# 19-100M_Ethernet.net
KiCad netlist of a schematic drawn in Altium Designer
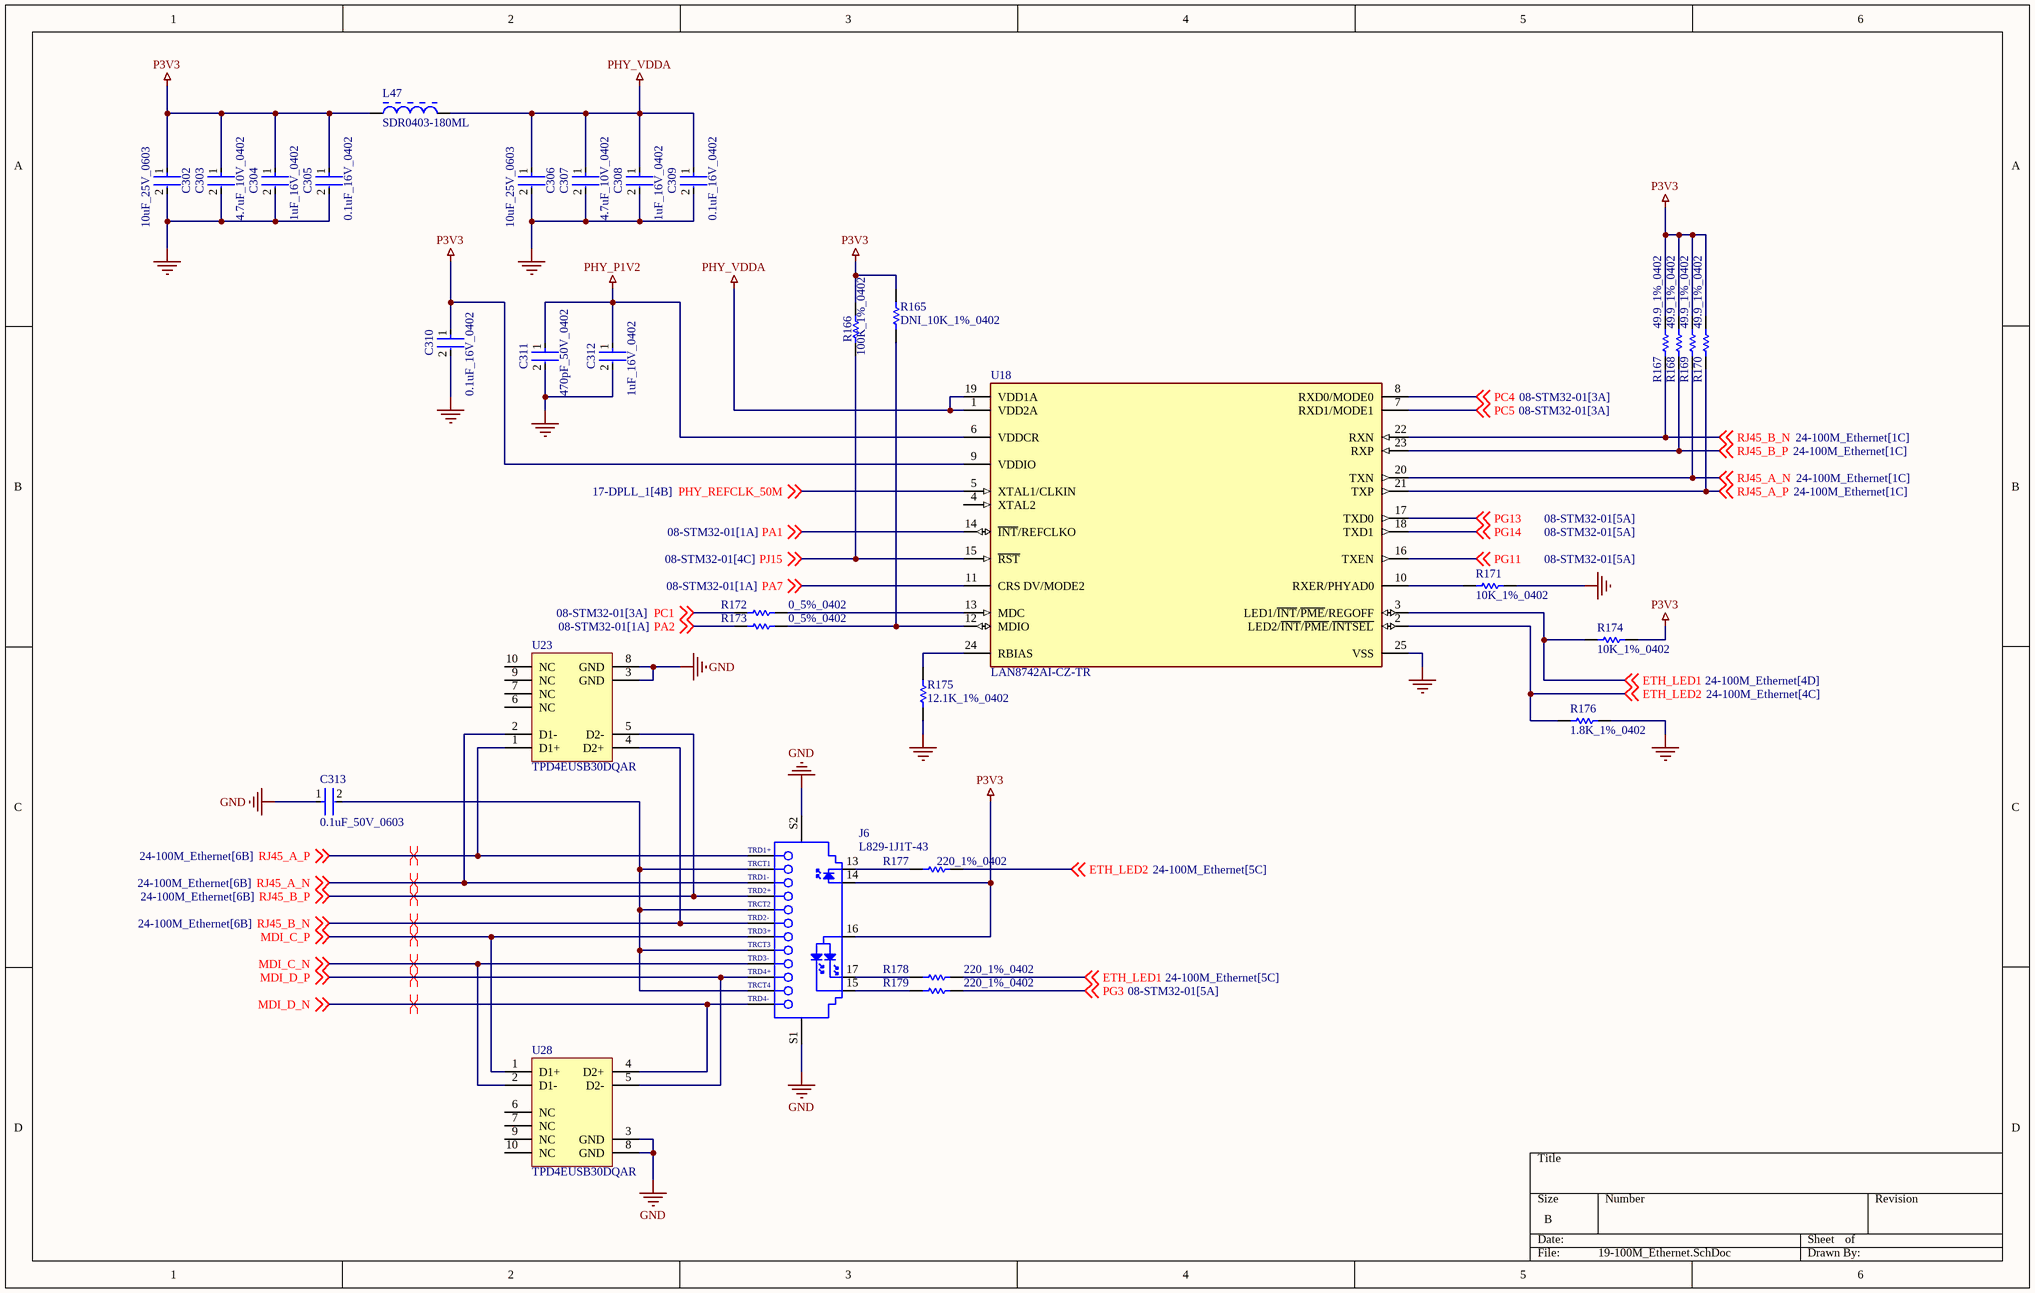
[diagram p0: 19-100M_Ethernet.SchDoc]

(export (version "E")
  (design (tool "Eeschema 10.0.6"))
  (components
    (comp (ref "C302")
      (value "10uF_25V_0603")
      (footprint "FP-CL10-IPC_C")
      (description "Cap Ceramic 10uF 25V X5R ±20% Pad SMD 0603 +85°C T/R")
      (fields (field (name "TOLERANCE") "20%"))
      (libsource (lib "Altium Content Vault") (part "b4654b650e69147ec39a6b967a45e02"))
    )
    (comp (ref "C303")
      (value "4.7uF_10V_0402")
      (footprint "FP-C1005-050-0_15-MFG")
      (description "CAP CER 4.7UF 10V X5R 0402")
      (fields (field (name "TOLERANCE") "10%"))
      (libsource (lib "Altium Content Vault") (part "b4654b650e69147ec39a6b967a45e02"))
    )
    (comp (ref "C304")
      (value "1uF_16V_0402")
      (footprint "FP-0402-L_1_0_0_05-W_0_5-IPC_A")
      (description "None")
      (fields (field (name "TOLERANCE") "10%"))
      (libsource (lib "Altium Content Vault") (part "b4654b650e69147ec39a6b967a45e02"))
    )
    (comp (ref "C305")
      (value "0.1uF_16V_0402")
      (footprint "FP-C0402-BB-MFG")
      (description "CAP CER 0.1UF 16V 5% X7R 0402")
      (fields
        (field (name "MANUFACTURER") "Kemet")
        (field (name "MANUFACTURER PART NUMBER") "C0402C104J4RACTU")
      )
      (libsource (lib "Altium Content Vault") (part "b4654b650e69147ec39a6b967a45e02"))
    )
    (comp (ref "C306")
      (value "10uF_25V_0603")
      (footprint "FP-CL10-IPC_C")
      (description "Cap Ceramic 10uF 25V X5R ±20% Pad SMD 0603 +85°C T/R")
      (fields (field (name "TOLERANCE") "20%"))
      (libsource (lib "Altium Content Vault") (part "b4654b650e69147ec39a6b967a45e02"))
    )
    (comp (ref "C307")
      (value "4.7uF_10V_0402")
      (footprint "FP-C1005-050-0_15-MFG")
      (description "CAP CER 4.7UF 10V X5R 0402")
      (fields (field (name "TOLERANCE") "10%"))
      (libsource (lib "Altium Content Vault") (part "b4654b650e69147ec39a6b967a45e02"))
    )
    (comp (ref "C308")
      (value "1uF_16V_0402")
      (footprint "FP-0402-L_1_0_0_05-W_0_5-IPC_A")
      (description "None")
      (fields (field (name "TOLERANCE") "10%"))
      (libsource (lib "Altium Content Vault") (part "b4654b650e69147ec39a6b967a45e02"))
    )
    (comp (ref "C309")
      (value "0.1uF_16V_0402")
      (footprint "FP-C0402-BB-MFG")
      (description "CAP CER 0.1UF 16V 5% X7R 0402")
      (fields
        (field (name "MANUFACTURER") "Kemet")
        (field (name "MANUFACTURER PART NUMBER") "C0402C104J4RACTU")
      )
      (libsource (lib "Altium Content Vault") (part "b4654b650e69147ec39a6b967a45e02"))
    )
    (comp (ref "C310")
      (value "0.1uF_16V_0402")
      (footprint "FP-C0402-BB-MFG")
      (description "CAP CER 0.1UF 16V 5% X7R 0402")
      (fields
        (field (name "MANUFACTURER") "Kemet")
        (field (name "MANUFACTURER PART NUMBER") "C0402C104J4RACTU")
      )
      (libsource (lib "Altium Content Vault") (part "b4654b650e69147ec39a6b967a45e02"))
    )
    (comp (ref "C311")
      (value "470pF_50V_0402")
      (footprint "FP-GRM155-0_05-IPC_A")
      (description "Chip Multilayer Ceramic Capacitors for General Purpose, 0402, 470pF, C0G, 30ppm/°C, 5%, 50V")
      (fields (field (name "VOLTAGE") "50V") (field (name "TOLERANCE") "5%"))
      (libsource (lib "Altium Content Vault") (part "02cd4be3c70576c341d710602a673aa"))
    )
    (comp (ref "C312")
      (value "1uF_16V_0402")
      (footprint "FP-0402-L_1_0_0_05-W_0_5-IPC_A")
      (description "None")
      (fields (field (name "TOLERANCE") "10%"))
      (libsource (lib "Altium Content Vault") (part "b4654b650e69147ec39a6b967a45e02"))
    )
    (comp (ref "C313")
      (value "0.1uF_50V_0603")
      (footprint "FP-C0603-CJ-MFG")
      (description "CAP CER 0.1UF 50V X7R 0603")
      (fields (field (name "MANUFACTURER PART NUMBER") "C0603X104K5RACTU") (field (name "VOLTAGE") "50V"))
      (libsource (lib "Altium Content Vault") (part "11868f565c42a9108669ba33697ecf6"))
    )
    (comp (ref "J6")
      (value "L829-1J1T-43")
      (footprint "BELS-L829-1J1T-43_V")
      (description "Gigabit MagJack(R) Ultra Low Profile, 10/100/1000 Base-T, 19-Pin THD, RoHS, Tray")
      (libsource (lib "Altium Content Vault") (part "RJ45-17-2SHLD"))
    )
    (comp (ref "L47")
      (value "SDR0403-180ML")
      (footprint "BOUR-SDR0403-2_V")
      (fields (field (name "MANUFACTURER") "Bourns"))
      (libsource (lib "Altium Content Vault") (part "BOUR-IND-2A"))
    )
    (comp (ref "R165")
      (value "DNI_10K_1%_0402")
      (footprint "RESC1005X40X25NL10T10")
      (fields (field (name "MANUFACTURER") "Bourns") (field (name "PART NUMBER") "CR0402-FX-1002GLF"))
      (libsource (lib "Altium Content Vault") (part "RES"))
    )
    (comp (ref "R166")
      (value "100K_1%_0402")
      (footprint "RESC1005X40X25ML05T10")
      (fields (field (name "MANUFACTURER") "Yageo") (field (name "PART NUMBER") "RC0402FR-13100KL"))
      (libsource (lib "Altium Content Vault") (part "RES"))
    )
    (comp (ref "R167")
      (value "49.9_1%_0402")
      (footprint "RESC1005X40X25NL10T10")
      (fields (field (name "PART NUMBER") "RK73H1ETTP49R9F") (field (name "MANUFACTURER") "KOA Speer"))
      (libsource (lib "Altium Content Vault") (part "RES"))
    )
    (comp (ref "R168")
      (value "49.9_1%_0402")
      (footprint "RESC1005X40X25NL10T10")
      (fields (field (name "PART NUMBER") "RK73H1ETTP49R9F") (field (name "MANUFACTURER") "KOA Speer"))
      (libsource (lib "Altium Content Vault") (part "RES"))
    )
    (comp (ref "R169")
      (value "49.9_1%_0402")
      (footprint "RESC1005X40X25NL10T10")
      (fields (field (name "PART NUMBER") "RK73H1ETTP49R9F") (field (name "MANUFACTURER") "KOA Speer"))
      (libsource (lib "Altium Content Vault") (part "RES"))
    )
    (comp (ref "R170")
      (value "49.9_1%_0402")
      (footprint "RESC1005X40X25NL10T10")
      (fields (field (name "PART NUMBER") "RK73H1ETTP49R9F") (field (name "MANUFACTURER") "KOA Speer"))
      (libsource (lib "Altium Content Vault") (part "RES"))
    )
    (comp (ref "R171")
      (value "10K_1%_0402")
      (footprint "RESC1005X40X25NL10T10")
      (fields (field (name "MANUFACTURER") "Bourns") (field (name "PART NUMBER") "CR0402-FX-1002GLF"))
      (libsource (lib "Altium Content Vault") (part "RES"))
    )
    (comp (ref "R172")
      (value "0_5%_0402")
      (footprint "RESC1005X40X25NL05T10")
      (fields (field (name "MANUFACTURER") "Panasonic") (field (name "PART NUMBER") "ERJ-U020R00X"))
      (libsource (lib "Altium Content Vault") (part "RES"))
    )
    (comp (ref "R173")
      (value "0_5%_0402")
      (footprint "RESC1005X40X25NL05T10")
      (fields (field (name "MANUFACTURER") "Panasonic") (field (name "PART NUMBER") "ERJ-U020R00X"))
      (libsource (lib "Altium Content Vault") (part "RES"))
    )
    (comp (ref "R174")
      (value "10K_1%_0402")
      (footprint "RESC1005X40X25NL10T10")
      (fields (field (name "MANUFACTURER") "Bourns") (field (name "PART NUMBER") "CR0402-FX-1002GLF"))
      (libsource (lib "Altium Content Vault") (part "RES"))
    )
    (comp (ref "R175")
      (value "12.1K_1%_0402")
      (footprint "RESC1005X40X25ML05T10")
      (fields (field (name "PART NUMBER") "RC0402FR-0712K1L") (field (name "MANUFACTURER") "Yageo / Phycomp"))
      (libsource (lib "Altium Content Vault") (part "RES"))
    )
    (comp (ref "R176")
      (value "1.8K_1%_0402")
      (footprint "RESC1005X40X25LL05T05")
      (fields (field (name "MANUFACTURER") "Panasonic") (field (name "PART NUMBER") "ERJ2RKF1801X"))
      (libsource (lib "Altium Content Vault") (part "RES"))
    )
    (comp (ref "R177")
      (value "220_1%_0402")
      (footprint "RESC1005X40X25LL10T10")
      (fields (field (name "PART NUMBER") "RK73H1ETTP2200F") (field (name "MANUFACTURER") "KOA Speer"))
      (libsource (lib "Altium Content Vault") (part "RES"))
    )
    (comp (ref "R178")
      (value "220_1%_0402")
      (footprint "RESC1005X40X25LL10T10")
      (fields (field (name "PART NUMBER") "RK73H1ETTP2200F") (field (name "MANUFACTURER") "KOA Speer"))
      (libsource (lib "Altium Content Vault") (part "RES"))
    )
    (comp (ref "R179")
      (value "220_1%_0402")
      (footprint "RESC1005X40X25LL10T10")
      (fields (field (name "PART NUMBER") "RK73H1ETTP2200F") (field (name "MANUFACTURER") "KOA Speer"))
      (libsource (lib "Altium Content Vault") (part "RES"))
    )
    (comp (ref "U18")
      (value "LAN8742AI-CZ-TR")
      (footprint "FP-C04-143-MFG")
      (description "IC TRANSCEIVER FULL 1/1 24SQFN")
      (fields
        (field (name "MANUFACTURER") "Microchip")
        (field (name "OCTOPART") "https://octopart.com/lan8742ai-cz-tr-microchip-29030589")
      )
      (libsource (lib "Altium Content Vault") (part "663acb86b5908f69048389f16eb1286"))
    )
    (comp (ref "U23")
      (value "TPD4EUSB30DQAR")
      (footprint "DQA0010A_V")
      (fields (field (name "MANUFACTURER") "Texas Instruments"))
      (libsource (lib "") (part "TI-TPD4EUSB30-SON_DQA-10_1"))
    )
    (comp (ref "U28")
      (value "TPD4EUSB30DQAR")
      (footprint "DQA0010A_V")
      (fields (field (name "MANUFACTURER") "Texas Instruments"))
      (libsource (lib "Altium Content Vault") (part "TI-TPD4EUSB30-SON_DQA-10"))
    )
  )
  (nets
    (net (code "1") (name "ETH_LED1") (class "Default")
      (node (ref "R174") (pin "2") (pinfunction "2_2") (pintype "passive"))
      (node (ref "R178") (pin "2") (pinfunction "2_2") (pintype "passive"))
      (node (ref "U18") (pin "3") (pinfunction "LED1/~{INT}/~{PME}/REGOFF_3") (pintype "bidirectional"))
    )
    (net (code "2") (name "ETH_LED2") (class "Default")
      (node (ref "R176") (pin "1") (pinfunction "1_1") (pintype "passive"))
      (node (ref "R177") (pin "2") (pinfunction "2_2") (pintype "passive"))
      (node (ref "U18") (pin "2") (pinfunction "LED2/~{INT}/~{PME}/~{INTSEL}_2") (pintype "bidirectional"))
    )
    (net (code "3") (name "GND") (class "Default")
      (node (ref "C302") (pin "2") (pinfunction "2_2") (pintype "passive"))
      (node (ref "C303") (pin "2") (pinfunction "2_2") (pintype "passive"))
      (node (ref "C304") (pin "2") (pinfunction "2_2") (pintype "passive"))
      (node (ref "C305") (pin "2") (pinfunction "2_2") (pintype "passive"))
      (node (ref "C306") (pin "2") (pinfunction "2_2") (pintype "passive"))
      (node (ref "C307") (pin "2") (pinfunction "2_2") (pintype "passive"))
      (node (ref "C308") (pin "2") (pinfunction "2_2") (pintype "passive"))
      (node (ref "C309") (pin "2") (pinfunction "2_2") (pintype "passive"))
      (node (ref "C310") (pin "2") (pinfunction "2_2") (pintype "passive"))
      (node (ref "C311") (pin "2") (pinfunction "2_2") (pintype "passive"))
      (node (ref "C312") (pin "2") (pinfunction "2_2") (pintype "passive"))
      (node (ref "C313") (pin "1") (pinfunction "1_1") (pintype "passive"))
      (node (ref "J6") (pin "S1") (pinfunction "S1_S1") (pintype "passive"))
      (node (ref "J6") (pin "S2") (pinfunction "S2_S2") (pintype "passive"))
      (node (ref "R171") (pin "1") (pinfunction "1_1") (pintype "passive"))
      (node (ref "R175") (pin "1") (pinfunction "1_1") (pintype "passive"))
      (node (ref "R176") (pin "2") (pinfunction "2_2") (pintype "passive"))
      (node (ref "U18") (pin "25") (pinfunction "VSS_25") (pintype "power_in"))
      (node (ref "U23") (pin "3") (pinfunction "GND_3") (pintype "power_in"))
      (node (ref "U23") (pin "8") (pinfunction "GND_8") (pintype "power_in"))
      (node (ref "U28") (pin "3") (pinfunction "GND_3") (pintype "power_in"))
      (node (ref "U28") (pin "8") (pinfunction "GND_8") (pintype "power_in"))
    )
    (net (code "4") (name "MDI_C_N") (class "Default")
      (node (ref "J6") (pin "9") (pinfunction "TRD3-_9") (pintype "passive"))
      (node (ref "U28") (pin "2") (pinfunction "D1-_2") (pintype "passive"))
    )
    (net (code "5") (name "MDI_C_P") (class "Default")
      (node (ref "J6") (pin "7") (pinfunction "TRD3+_7") (pintype "passive"))
      (node (ref "U28") (pin "1") (pinfunction "D1+_1") (pintype "passive"))
    )
    (net (code "6") (name "MDI_D_N") (class "Default")
      (node (ref "J6") (pin "12") (pinfunction "TRD4-_12") (pintype "passive"))
      (node (ref "U28") (pin "4") (pinfunction "D2+_4") (pintype "passive"))
    )
    (net (code "7") (name "MDI_D_P") (class "Default")
      (node (ref "J6") (pin "10") (pinfunction "TRD4+_10") (pintype "passive"))
      (node (ref "U28") (pin "5") (pinfunction "D2-_5") (pintype "passive"))
    )
    (net (code "8") (name "Net-(J6-Pad13)") (class "Default")
      (node (ref "J6") (pin "13") (pinfunction "13_13") (pintype "passive"))
      (node (ref "R177") (pin "1") (pinfunction "1_1") (pintype "passive"))
    )
    (net (code "9") (name "Net-(J6-Pad15)") (class "Default")
      (node (ref "J6") (pin "15") (pinfunction "15_15") (pintype "passive"))
      (node (ref "R179") (pin "1") (pinfunction "1_1") (pintype "passive"))
    )
    (net (code "10") (name "Net-(J6-Pad17)") (class "Default")
      (node (ref "J6") (pin "17") (pinfunction "17_17") (pintype "passive"))
      (node (ref "R178") (pin "1") (pinfunction "1_1") (pintype "passive"))
    )
    (net (code "11") (name "Net-(J6-TRCT1)") (class "Default")
      (node (ref "C313") (pin "2") (pinfunction "2_2") (pintype "passive"))
      (node (ref "J6") (pin "11") (pinfunction "TRCT4_11") (pintype "passive"))
      (node (ref "J6") (pin "2") (pinfunction "TRCT1_2") (pintype "passive"))
      (node (ref "J6") (pin "5") (pinfunction "TRCT2_5") (pintype "passive"))
      (node (ref "J6") (pin "8") (pinfunction "TRCT3_8") (pintype "passive"))
    )
    (net (code "12") (name "Net-(U18-MDC)") (class "Default")
      (node (ref "R172") (pin "2") (pinfunction "2_2") (pintype "passive"))
      (node (ref "U18") (pin "13") (pinfunction "MDC_13") (pintype "input"))
    )
    (net (code "13") (name "Net-(U18-MDIO)") (class "Default")
      (node (ref "R165") (pin "2") (pinfunction "2_2") (pintype "passive"))
      (node (ref "R173") (pin "2") (pinfunction "2_2") (pintype "passive"))
      (node (ref "U18") (pin "12") (pinfunction "MDIO_12") (pintype "bidirectional"))
    )
    (net (code "14") (name "Net-(U18-RBIAS)") (class "Default")
      (node (ref "R175") (pin "2") (pinfunction "2_2") (pintype "passive"))
      (node (ref "U18") (pin "24") (pinfunction "RBIAS_24") (pintype "passive"))
    )
    (net (code "15") (name "Net-(U18-RXER{slash}PHYAD0)") (class "Default")
      (node (ref "R171") (pin "2") (pinfunction "2_2") (pintype "passive"))
      (node (ref "U18") (pin "10") (pinfunction "RXER/PHYAD0_10") (pintype "passive"))
    )
    (net (code "16") (name "P3V3") (class "Default")
      (node (ref "C302") (pin "1") (pinfunction "1_1") (pintype "passive"))
      (node (ref "C303") (pin "1") (pinfunction "1_1") (pintype "passive"))
      (node (ref "C304") (pin "1") (pinfunction "1_1") (pintype "passive"))
      (node (ref "C305") (pin "1") (pinfunction "1_1") (pintype "passive"))
      (node (ref "C310") (pin "1") (pinfunction "1_1") (pintype "passive"))
      (node (ref "J6") (pin "14") (pinfunction "14_14") (pintype "passive"))
      (node (ref "J6") (pin "16") (pinfunction "16_16") (pintype "passive"))
      (node (ref "L47") (pin "1") (pinfunction "1_1") (pintype "passive"))
      (node (ref "R165") (pin "1") (pinfunction "1_1") (pintype "passive"))
      (node (ref "R166") (pin "2") (pinfunction "2_2") (pintype "passive"))
      (node (ref "R167") (pin "1") (pinfunction "1_1") (pintype "passive"))
      (node (ref "R168") (pin "1") (pinfunction "1_1") (pintype "passive"))
      (node (ref "R169") (pin "1") (pinfunction "1_1") (pintype "passive"))
      (node (ref "R170") (pin "1") (pinfunction "1_1") (pintype "passive"))
      (node (ref "R174") (pin "1") (pinfunction "1_1") (pintype "passive"))
      (node (ref "U18") (pin "9") (pinfunction "VDDIO_9") (pintype "power_in"))
    )
    (net (code "17") (name "PA1") (class "Default")
      (node (ref "U18") (pin "14") (pinfunction "~{INT}/REFCLKO_14") (pintype "bidirectional"))
    )
    (net (code "18") (name "PA2") (class "Default")
      (node (ref "R173") (pin "1") (pinfunction "1_1") (pintype "passive"))
    )
    (net (code "19") (name "PA7") (class "Default")
      (node (ref "U18") (pin "11") (pinfunction "CRS_DV/MODE2_11") (pintype "passive"))
    )
    (net (code "20") (name "PC1") (class "Default")
      (node (ref "R172") (pin "1") (pinfunction "1_1") (pintype "passive"))
    )
    (net (code "21") (name "PC4") (class "Default")
      (node (ref "U18") (pin "8") (pinfunction "RXD0/MODE0_8") (pintype "passive"))
    )
    (net (code "22") (name "PC5") (class "Default")
      (node (ref "U18") (pin "7") (pinfunction "RXD1/MODE1_7") (pintype "passive"))
    )
    (net (code "23") (name "PG3") (class "Default")
      (node (ref "R179") (pin "2") (pinfunction "2_2") (pintype "passive"))
    )
    (net (code "24") (name "PG11") (class "Default")
      (node (ref "U18") (pin "16") (pinfunction "TXEN_16") (pintype "output"))
    )
    (net (code "25") (name "PG13") (class "Default")
      (node (ref "U18") (pin "17") (pinfunction "TXD0_17") (pintype "output"))
    )
    (net (code "26") (name "PG14") (class "Default")
      (node (ref "U18") (pin "18") (pinfunction "TXD1_18") (pintype "output"))
    )
    (net (code "27") (name "PHY_P1V2") (class "Default")
      (node (ref "C311") (pin "1") (pinfunction "1_1") (pintype "passive"))
      (node (ref "C312") (pin "1") (pinfunction "1_1") (pintype "passive"))
      (node (ref "U18") (pin "6") (pinfunction "VDDCR_6") (pintype "power_in"))
    )
    (net (code "28") (name "PHY_REFCLK_50M") (class "Default")
      (node (ref "U18") (pin "5") (pinfunction "XTAL1/CLKIN_5") (pintype "input"))
    )
    (net (code "29") (name "PHY_VDDA") (class "Default")
      (node (ref "C306") (pin "1") (pinfunction "1_1") (pintype "passive"))
      (node (ref "C307") (pin "1") (pinfunction "1_1") (pintype "passive"))
      (node (ref "C308") (pin "1") (pinfunction "1_1") (pintype "passive"))
      (node (ref "C309") (pin "1") (pinfunction "1_1") (pintype "passive"))
      (node (ref "L47") (pin "2") (pinfunction "2_2") (pintype "passive"))
      (node (ref "U18") (pin "1") (pinfunction "VDD2A_1") (pintype "power_in"))
      (node (ref "U18") (pin "19") (pinfunction "VDD1A_19") (pintype "power_in"))
    )
    (net (code "30") (name "PJ15") (class "Default")
      (node (ref "R166") (pin "1") (pinfunction "1_1") (pintype "passive"))
      (node (ref "U18") (pin "15") (pinfunction "~{RST}_15") (pintype "input"))
    )
    (net (code "31") (name "RJ45_A_N") (class "Default")
      (node (ref "J6") (pin "3") (pinfunction "TRD1-_3") (pintype "passive"))
      (node (ref "R169") (pin "2") (pinfunction "2_2") (pintype "passive"))
      (node (ref "U18") (pin "20") (pinfunction "TXN_20") (pintype "output"))
      (node (ref "U23") (pin "2") (pinfunction "D1-_2") (pintype "passive"))
    )
    (net (code "32") (name "RJ45_A_P") (class "Default")
      (node (ref "J6") (pin "1") (pinfunction "TRD1+_1") (pintype "passive"))
      (node (ref "R170") (pin "2") (pinfunction "2_2") (pintype "passive"))
      (node (ref "U18") (pin "21") (pinfunction "TXP_21") (pintype "output"))
      (node (ref "U23") (pin "1") (pinfunction "D1+_1") (pintype "passive"))
    )
    (net (code "33") (name "RJ45_B_N") (class "Default")
      (node (ref "J6") (pin "6") (pinfunction "TRD2-_6") (pintype "passive"))
      (node (ref "R167") (pin "2") (pinfunction "2_2") (pintype "passive"))
      (node (ref "U18") (pin "22") (pinfunction "RXN_22") (pintype "input"))
      (node (ref "U23") (pin "4") (pinfunction "D2+_4") (pintype "passive"))
    )
    (net (code "34") (name "RJ45_B_P") (class "Default")
      (node (ref "J6") (pin "4") (pinfunction "TRD2+_4") (pintype "passive"))
      (node (ref "R168") (pin "2") (pinfunction "2_2") (pintype "passive"))
      (node (ref "U18") (pin "23") (pinfunction "RXP_23") (pintype "input"))
      (node (ref "U23") (pin "5") (pinfunction "D2-_5") (pintype "passive"))
    )
    (net (code "35") (name "unconnected-(U18-XTAL2-Pad4)") (class "Default")
      (node (ref "U18") (pin "4") (pinfunction "XTAL2_4") (pintype "input"))
    )
    (net (code "36") (name "unconnected-(U23-NC-Pad6)") (class "Default")
      (node (ref "U23") (pin "6") (pinfunction "NC_6") (pintype "passive"))
    )
    (net (code "37") (name "unconnected-(U23-NC-Pad7)") (class "Default")
      (node (ref "U23") (pin "7") (pinfunction "NC_7") (pintype "passive"))
    )
    (net (code "38") (name "unconnected-(U23-NC-Pad9)") (class "Default")
      (node (ref "U23") (pin "9") (pinfunction "NC_9") (pintype "passive"))
    )
    (net (code "39") (name "unconnected-(U23-NC-Pad10)") (class "Default")
      (node (ref "U23") (pin "10") (pinfunction "NC_10") (pintype "passive"))
    )
    (net (code "40") (name "unconnected-(U28-NC-Pad6)") (class "Default")
      (node (ref "U28") (pin "6") (pinfunction "NC_6") (pintype "passive"))
    )
    (net (code "41") (name "unconnected-(U28-NC-Pad7)") (class "Default")
      (node (ref "U28") (pin "7") (pinfunction "NC_7") (pintype "passive"))
    )
    (net (code "42") (name "unconnected-(U28-NC-Pad9)") (class "Default")
      (node (ref "U28") (pin "9") (pinfunction "NC_9") (pintype "passive"))
    )
    (net (code "43") (name "unconnected-(U28-NC-Pad10)") (class "Default")
      (node (ref "U28") (pin "10") (pinfunction "NC_10") (pintype "passive"))
    )
  )
)
